# Audio.net
KiCad netlist of a schematic drawn in Altium Designer
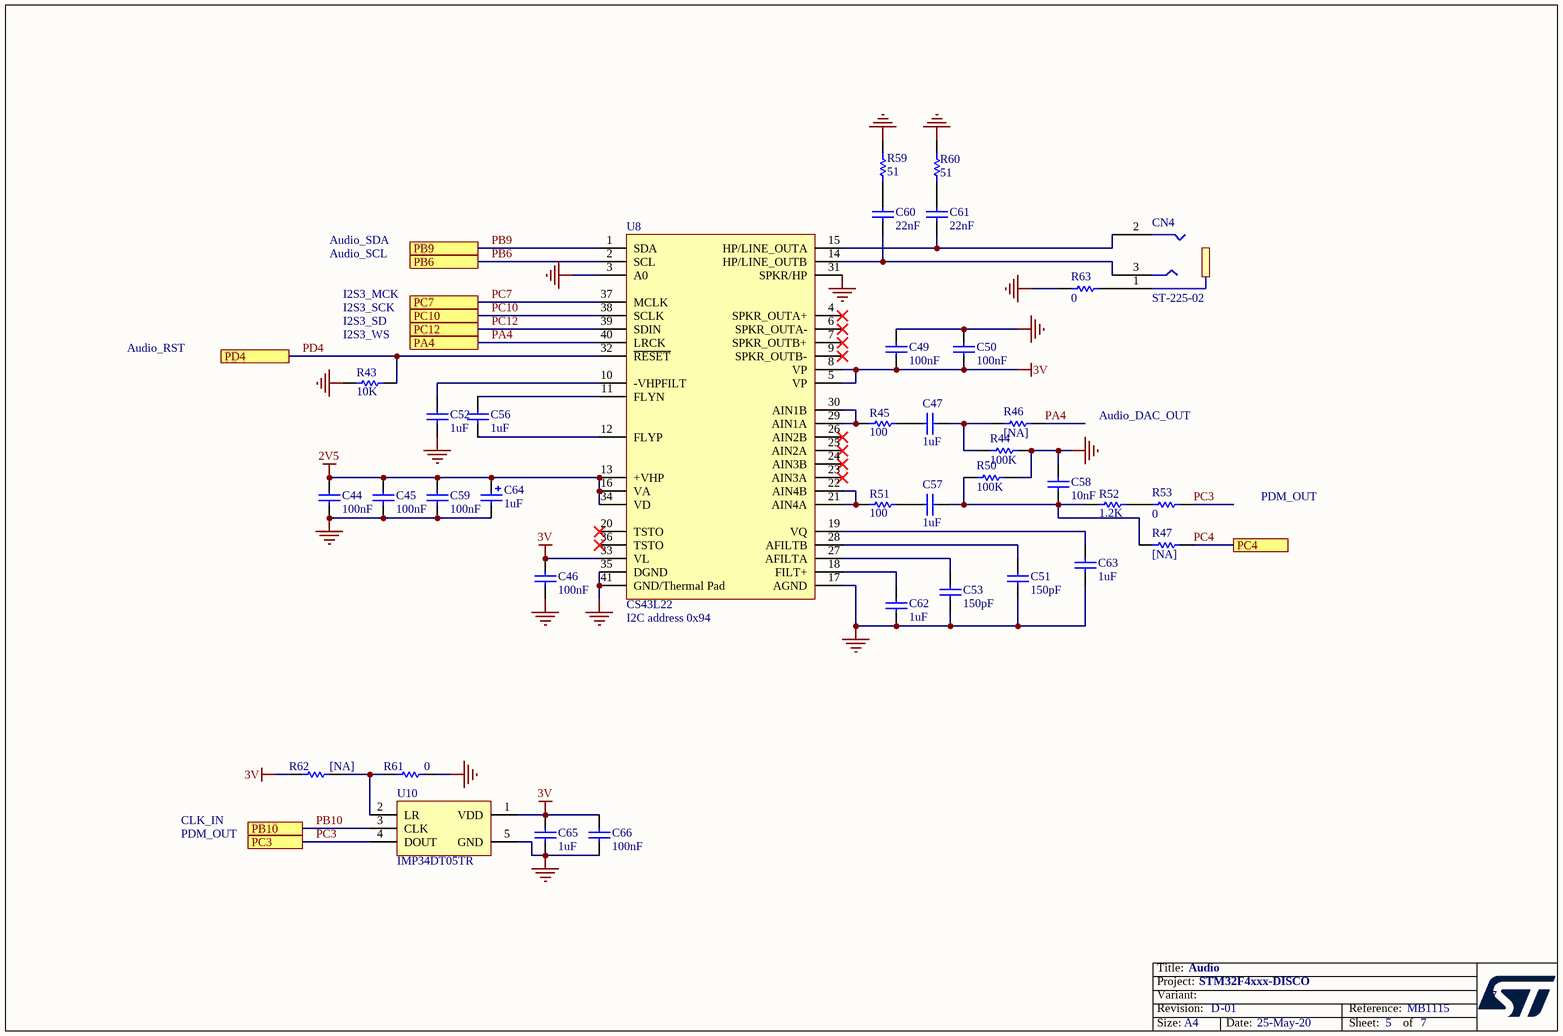
[diagram p0: Audio.SchDoc]

(export (version "E")
  (design (tool "Eeschema 10.0.6"))
  (components
    (comp (ref "C44")
      (value "100nF")
      (footprint "0402C (Primary)")
      (description "Capacitor,100nF,16V,X7R,10%,0402,YAGEO")
      (libsource (lib "MCD_TOOLS") (part "Cap_100nF_X7R_10%_0402"))
    )
    (comp (ref "C45")
      (value "100nF")
      (footprint "0402C (Primary)")
      (description "Capacitor,100nF,16V,X7R,10%,0402,YAGEO")
      (libsource (lib "MCD_TOOLS") (part "Cap_100nF_X7R_10%_0402"))
    )
    (comp (ref "C46")
      (value "100nF")
      (footprint "0402C (Primary)")
      (description "Capacitor,100nF,16V,X7R,10%,0402,YAGEO")
      (libsource (lib "MCD_TOOLS") (part "Cap_100nF_X7R_10%_0402"))
    )
    (comp (ref "C47")
      (value "1uF")
      (footprint "0603C (Primary)")
      (description "Capacitor,1uF,16V,X5R,10%,0603,YAGEO")
      (libsource (lib "MCD_TOOLS") (part "Cap_1uF_X5R_10%_0603"))
    )
    (comp (ref "C49")
      (value "100nF")
      (footprint "0402C (Primary)")
      (description "Capacitor,100nF,16V,X7R,10%,0402,YAGEO")
      (libsource (lib "MCD_TOOLS") (part "Cap_100nF_X7R_10%_0402"))
    )
    (comp (ref "C50")
      (value "100nF")
      (footprint "0402C (Primary)")
      (description "Capacitor,100nF,16V,X7R,10%,0402,YAGEO")
      (libsource (lib "MCD_TOOLS") (part "Cap_100nF_X7R_10%_0402"))
    )
    (comp (ref "C51")
      (value "150pF")
      (footprint "0603C (Primary)")
      (description "Capacitor,150pF,50V,NPO,5%,0603,YAGEO")
      (libsource (lib "MCD_TOOLS") (part "Cap_150pF_NPO_5%_0603"))
    )
    (comp (ref "C52")
      (value "1uF")
      (footprint "0603C (Primary)")
      (description "Capacitor,1uF,16V,X5R,10%,0603,YAGEO")
      (libsource (lib "MCD_TOOLS") (part "Cap_1uF_X5R_10%_0603"))
    )
    (comp (ref "C53")
      (value "150pF")
      (footprint "0603C (Primary)")
      (description "Capacitor,150pF,50V,NPO,5%,0603,YAGEO")
      (libsource (lib "MCD_TOOLS") (part "Cap_150pF_NPO_5%_0603"))
    )
    (comp (ref "C56")
      (value "1uF")
      (footprint "0603C (Primary)")
      (description "Capacitor,1uF,16V,X5R,10%,0603,YAGEO")
      (libsource (lib "MCD_TOOLS") (part "Cap_1uF_X5R_10%_0603"))
    )
    (comp (ref "C57")
      (value "1uF")
      (footprint "0603C (Primary)")
      (description "Capacitor,1uF,16V,X5R,10%,0603,YAGEO")
      (libsource (lib "MCD_TOOLS") (part "Cap_1uF_X5R_10%_0603"))
    )
    (comp (ref "C58")
      (value "10nF")
      (footprint "0603C (Primary)")
      (description "Capacitor,10nF,50V,X7R,10%,0603,YAGEO")
      (libsource (lib "MCD_TOOLS") (part "Cap_10nF_X7R_10%_0603"))
    )
    (comp (ref "C59")
      (value "100nF")
      (footprint "0402C (Primary)")
      (description "Capacitor,100nF,16V,X7R,10%,0402,YAGEO")
      (libsource (lib "MCD_TOOLS") (part "Cap_100nF_X7R_10%_0402"))
    )
    (comp (ref "C60")
      (value "22nF")
      (footprint "0603C (Primary)")
      (description "Capacitor,22nF,50V,X7R,10%,0603,YAGEO")
      (libsource (lib "MCD_TOOLS") (part "Cap_22nF_X7R_10%_0603"))
    )
    (comp (ref "C61")
      (value "22nF")
      (footprint "0603C (Primary)")
      (description "Capacitor,22nF,50V,X7R,10%,0603,YAGEO")
      (libsource (lib "MCD_TOOLS") (part "Cap_22nF_X7R_10%_0603"))
    )
    (comp (ref "C62")
      (value "1uF")
      (footprint "0603C (Primary)")
      (description "Capacitor,1uF,16V,X5R,10%,0603,YAGEO")
      (libsource (lib "MCD_TOOLS") (part "Cap_1uF_X5R_10%_0603"))
    )
    (comp (ref "C63")
      (value "1uF")
      (footprint "0603C (Primary)")
      (description "Capacitor,1uF,16V,X5R,10%,0603,YAGEO")
      (libsource (lib "MCD_TOOLS") (part "Cap_1uF_X5R_10%_0603"))
    )
    (comp (ref "C64")
      (value "1uF")
      (footprint "TAN-A (Primary)")
      (description "Polarized Capacitor,1uF,16V,10%,typeA,AVX")
      (libsource (lib "MCD_TOOLS") (part "Cap_1uF_POL_10%_TANA"))
    )
    (comp (ref "C65")
      (value "1uF")
      (footprint "0603C (Primary)")
      (description "Capacitor,1uF,16V,X5R,10%,0603,YAGEO")
      (libsource (lib "MCD_TOOLS") (part "Cap_1uF_X5R_10%_0603"))
    )
    (comp (ref "C66")
      (value "100nF")
      (footprint "0402C (Primary)")
      (description "Capacitor,100nF,16V,X7R,10%,0402,YAGEO")
      (libsource (lib "MCD_TOOLS") (part "Cap_100nF_X7R_10%_0402"))
    )
    (comp (ref "CN4")
      (value "ST-225-02")
      (footprint "JACK-ST-225 (Primary)")
      (description "Connector Jack 35mm")
      (libsource (lib "MB997") (part "ST-225-02"))
    )
    (comp (ref "R43")
      (value "10K")
      (footprint "0402R (Primary)")
      (description "Resistor")
      (fields (field (name "PUBLISHER") "Altium Limited"))
      (libsource (lib "Miscellaneous Devices") (part "res1"))
    )
    (comp (ref "R44")
      (value "100K")
      (footprint "0402R (Primary)")
      (description "Resistor")
      (fields (field (name "PUBLISHER") "Altium Limited"))
      (libsource (lib "Miscellaneous Devices") (part "res1"))
    )
    (comp (ref "R45")
      (value "100")
      (footprint "0402R (Primary)")
      (description "Resistor")
      (fields (field (name "PUBLISHER") "Altium Limited"))
      (libsource (lib "Miscellaneous Devices") (part "res1"))
    )
    (comp (ref "R46")
      (value "[NA]")
      (footprint "0402R (Primary)")
      (description "Resistor,[NA],0402")
      (libsource (lib "MCD_TOOLS") (part "Res_NA_0402"))
    )
    (comp (ref "R47")
      (value "[NA]")
      (footprint "0402R (Primary)")
      (description "Resistor,[NA],0402")
      (libsource (lib "MCD_TOOLS") (part "Res_NA_0402"))
    )
    (comp (ref "R50")
      (value "100K")
      (footprint "0402R (Primary)")
      (description "Resistor")
      (fields (field (name "PUBLISHER") "Altium Limited"))
      (libsource (lib "Miscellaneous Devices") (part "res1"))
    )
    (comp (ref "R51")
      (value "100")
      (footprint "0402R (Primary)")
      (description "Resistor")
      (fields (field (name "PUBLISHER") "Altium Limited"))
      (libsource (lib "Miscellaneous Devices") (part "res1"))
    )
    (comp (ref "R52")
      (value "1.2K")
      (footprint "0402R (Primary)")
      (description "Resistor")
      (fields (field (name "PUBLISHER") "Altium Limited"))
      (libsource (lib "Miscellaneous Devices") (part "res1"))
    )
    (comp (ref "R53")
      (value "0")
      (footprint "0402R (Primary)")
      (description "Resistor,0,0402")
      (libsource (lib "MCD_TOOLS") (part "Res_0_0402"))
    )
    (comp (ref "R59")
      (value "51")
      (footprint "0402R (Primary)")
      (description "Resistor")
      (fields (field (name "PUBLISHER") "Altium Limited"))
      (libsource (lib "Miscellaneous Devices") (part "res1"))
    )
    (comp (ref "R60")
      (value "51")
      (footprint "0402R (Primary)")
      (description "Resistor")
      (fields (field (name "PUBLISHER") "Altium Limited"))
      (libsource (lib "Miscellaneous Devices") (part "res1"))
    )
    (comp (ref "R61")
      (value "0")
      (footprint "0402R (Primary)")
      (description "Resistor,0,0402")
      (libsource (lib "MCD_TOOLS") (part "Res_0_0402"))
    )
    (comp (ref "R62")
      (value "[NA]")
      (footprint "0402R (Primary)")
      (description "Resistor,[NA],0402")
      (libsource (lib "MCD_TOOLS") (part "Res_NA_0402"))
    )
    (comp (ref "R63")
      (value "0")
      (footprint "0402R (Primary)")
      (description "Resistor,0,0402")
      (libsource (lib "MCD_TOOLS") (part "Res_0_0402"))
    )
    (comp (ref "U8")
      (value "CS43L22")
      (footprint "QFN40_6X6 (Primary)")
      (description "Low Power, Stereo DAC w/Headphone & Speaker Amps")
      (libsource (lib "MCD_TOOLS") (part "CS43L22"))
    )
    (comp (ref "U10")
      (value "IMP34DT05TR")
      (footprint "MIC_HCLGA_3X4X1_4LD")
      (description "MEMS audio sensor omnidirectional digital microphone for industrial applications")
      (fields
        (field (name "INTERNAL_PART_NUMBER") "MCD-01715")
        (field (name "MANUFACTURER") "STMICROELECTRONICS")
        (field (name "PROVIDED_BY") "SUBCO with ST control")
      )
      (libsource (lib "MCD_PARTS_database") (part "IMP34DT05TR"))
    )
  )
  (nets
    (net (code "1") (name "/PA4") (class "Default")
      (node (ref "R46") (pin "2") (pinfunction "2_2") (pintype "passive"))
      (node (ref "U8") (pin "40") (pinfunction "LRCK_40") (pintype "passive"))
    )
    (net (code "2") (name "/PB6") (class "Default")
      (node (ref "U8") (pin "2") (pinfunction "SCL_2") (pintype "passive"))
    )
    (net (code "3") (name "/PB9") (class "Default")
      (node (ref "U8") (pin "1") (pinfunction "SDA_1") (pintype "passive"))
    )
    (net (code "4") (name "/PB10") (class "Default")
      (node (ref "U10") (pin "3") (pinfunction "CLK_3") (pintype "passive"))
    )
    (net (code "5") (name "/PC3") (class "Default")
      (node (ref "R53") (pin "2") (pinfunction "2_2") (pintype "passive"))
      (node (ref "U10") (pin "4") (pinfunction "DOUT_4") (pintype "passive"))
    )
    (net (code "6") (name "/PC4") (class "Default")
      (node (ref "R47") (pin "2") (pinfunction "2_2") (pintype "passive"))
    )
    (net (code "7") (name "/PC7") (class "Default")
      (node (ref "U8") (pin "37") (pinfunction "MCLK_37") (pintype "passive"))
    )
    (net (code "8") (name "/PC10") (class "Default")
      (node (ref "U8") (pin "38") (pinfunction "SCLK_38") (pintype "passive"))
    )
    (net (code "9") (name "/PC12") (class "Default")
      (node (ref "U8") (pin "39") (pinfunction "SDIN_39") (pintype "passive"))
    )
    (net (code "10") (name "/PD4") (class "Default")
      (node (ref "R43") (pin "1") (pinfunction "1_1") (pintype "passive"))
      (node (ref "U8") (pin "32") (pinfunction "~{RESET}_32") (pintype "passive"))
    )
    (net (code "11") (name "2V5") (class "Default")
      (node (ref "C44") (pin "2") (pinfunction "2_2") (pintype "passive"))
      (node (ref "C45") (pin "2") (pinfunction "2_2") (pintype "passive"))
      (node (ref "C59") (pin "2") (pinfunction "2_2") (pintype "passive"))
      (node (ref "C64") (pin "1") (pinfunction "1_1") (pintype "passive"))
      (node (ref "U8") (pin "13") (pinfunction "+VHP_13") (pintype "passive"))
      (node (ref "U8") (pin "16") (pinfunction "VA_16") (pintype "passive"))
      (node (ref "U8") (pin "34") (pinfunction "VD_34") (pintype "passive"))
    )
    (net (code "12") (name "3V") (class "Default")
      (node (ref "C46") (pin "2") (pinfunction "2_2") (pintype "passive"))
      (node (ref "C49") (pin "1") (pinfunction "1_1") (pintype "passive"))
      (node (ref "C50") (pin "2") (pinfunction "2_2") (pintype "passive"))
      (node (ref "C65") (pin "2") (pinfunction "2_2") (pintype "passive"))
      (node (ref "C66") (pin "2") (pinfunction "2_2") (pintype "passive"))
      (node (ref "R62") (pin "2") (pinfunction "2_2") (pintype "passive"))
      (node (ref "U10") (pin "1") (pinfunction "VDD_1") (pintype "passive"))
      (node (ref "U8") (pin "33") (pinfunction "VL_33") (pintype "passive"))
      (node (ref "U8") (pin "5") (pinfunction "VP_5") (pintype "passive"))
      (node (ref "U8") (pin "8") (pinfunction "VP_8") (pintype "passive"))
    )
    (net (code "13") (name "GND") (class "Default")
      (node (ref "C44") (pin "1") (pinfunction "1_1") (pintype "passive"))
      (node (ref "C45") (pin "1") (pinfunction "1_1") (pintype "passive"))
      (node (ref "C46") (pin "1") (pinfunction "1_1") (pintype "passive"))
      (node (ref "C49") (pin "2") (pinfunction "2_2") (pintype "passive"))
      (node (ref "C50") (pin "1") (pinfunction "1_1") (pintype "passive"))
      (node (ref "C51") (pin "1") (pinfunction "1_1") (pintype "passive"))
      (node (ref "C52") (pin "2") (pinfunction "2_2") (pintype "passive"))
      (node (ref "C53") (pin "1") (pinfunction "1_1") (pintype "passive"))
      (node (ref "C58") (pin "2") (pinfunction "2_2") (pintype "passive"))
      (node (ref "C59") (pin "1") (pinfunction "1_1") (pintype "passive"))
      (node (ref "C62") (pin "1") (pinfunction "1_1") (pintype "passive"))
      (node (ref "C63") (pin "1") (pinfunction "1_1") (pintype "passive"))
      (node (ref "C64") (pin "2") (pinfunction "2_2") (pintype "passive"))
      (node (ref "C65") (pin "1") (pinfunction "1_1") (pintype "passive"))
      (node (ref "C66") (pin "1") (pinfunction "1_1") (pintype "passive"))
      (node (ref "R43") (pin "2") (pinfunction "2_2") (pintype "passive"))
      (node (ref "R44") (pin "2") (pinfunction "2_2") (pintype "passive"))
      (node (ref "R50") (pin "2") (pinfunction "2_2") (pintype "passive"))
      (node (ref "R59") (pin "2") (pinfunction "2_2") (pintype "passive"))
      (node (ref "R60") (pin "1") (pinfunction "1_1") (pintype "passive"))
      (node (ref "R61") (pin "1") (pinfunction "1_1") (pintype "passive"))
      (node (ref "R63") (pin "1") (pinfunction "1_1") (pintype "passive"))
      (node (ref "U10") (pin "5") (pinfunction "GND_5") (pintype "passive"))
      (node (ref "U8") (pin "17") (pinfunction "AGND_17") (pintype "passive"))
      (node (ref "U8") (pin "3") (pinfunction "A0_3") (pintype "passive"))
      (node (ref "U8") (pin "31") (pinfunction "SPKR/HP_31") (pintype "passive"))
      (node (ref "U8") (pin "35") (pinfunction "DGND_35") (pintype "passive"))
      (node (ref "U8") (pin "41") (pinfunction "GND/Thermal_Pad_41") (pintype "passive"))
    )
    (net (code "14") (name "Net-(C47-Pad1)") (class "Default")
      (node (ref "C47") (pin "1") (pinfunction "1_1") (pintype "passive"))
      (node (ref "R45") (pin "1") (pinfunction "1_1") (pintype "passive"))
    )
    (net (code "15") (name "Net-(C47-Pad2)") (class "Default")
      (node (ref "C47") (pin "2") (pinfunction "2_2") (pintype "passive"))
      (node (ref "R44") (pin "1") (pinfunction "1_1") (pintype "passive"))
      (node (ref "R46") (pin "1") (pinfunction "1_1") (pintype "passive"))
    )
    (net (code "16") (name "Net-(C57-Pad1)") (class "Default")
      (node (ref "C57") (pin "1") (pinfunction "1_1") (pintype "passive"))
      (node (ref "R51") (pin "1") (pinfunction "1_1") (pintype "passive"))
    )
    (net (code "17") (name "Net-(C57-Pad2)") (class "Default")
      (node (ref "C57") (pin "2") (pinfunction "2_2") (pintype "passive"))
      (node (ref "C58") (pin "1") (pinfunction "1_1") (pintype "passive"))
      (node (ref "R47") (pin "1") (pinfunction "1_1") (pintype "passive"))
      (node (ref "R50") (pin "1") (pinfunction "1_1") (pintype "passive"))
      (node (ref "R52") (pin "1") (pinfunction "1_1") (pintype "passive"))
    )
    (net (code "18") (name "Net-(C60-Pad2)") (class "Default")
      (node (ref "C60") (pin "2") (pinfunction "2_2") (pintype "passive"))
      (node (ref "R59") (pin "1") (pinfunction "1_1") (pintype "passive"))
    )
    (net (code "19") (name "Net-(C61-Pad2)") (class "Default")
      (node (ref "C61") (pin "2") (pinfunction "2_2") (pintype "passive"))
      (node (ref "R60") (pin "2") (pinfunction "2_2") (pintype "passive"))
    )
    (net (code "20") (name "Net-(CN4-Pad1)") (class "Default")
      (node (ref "CN4") (pin "1") (pintype "passive"))
      (node (ref "R63") (pin "2") (pinfunction "2_2") (pintype "passive"))
    )
    (net (code "21") (name "Net-(R52-Pad2)") (class "Default")
      (node (ref "R52") (pin "2") (pinfunction "2_2") (pintype "passive"))
      (node (ref "R53") (pin "1") (pinfunction "1_1") (pintype "passive"))
    )
    (net (code "22") (name "Net-(U8--VHPFILT)") (class "Default")
      (node (ref "C52") (pin "1") (pinfunction "1_1") (pintype "passive"))
      (node (ref "U8") (pin "10") (pinfunction "-VHPFILT_10") (pintype "passive"))
    )
    (net (code "23") (name "Net-(U8-AFILTA)") (class "Default")
      (node (ref "C53") (pin "2") (pinfunction "2_2") (pintype "passive"))
      (node (ref "U8") (pin "27") (pinfunction "AFILTA_27") (pintype "passive"))
    )
    (net (code "24") (name "Net-(U8-AFILTB)") (class "Default")
      (node (ref "C51") (pin "2") (pinfunction "2_2") (pintype "passive"))
      (node (ref "U8") (pin "28") (pinfunction "AFILTB_28") (pintype "passive"))
    )
    (net (code "25") (name "Net-(U8-AIN1A)") (class "Default")
      (node (ref "R45") (pin "2") (pinfunction "2_2") (pintype "passive"))
      (node (ref "U8") (pin "29") (pinfunction "AIN1A_29") (pintype "passive"))
      (node (ref "U8") (pin "30") (pinfunction "AIN1B_30") (pintype "passive"))
    )
    (net (code "26") (name "Net-(U8-AIN4A)") (class "Default")
      (node (ref "R51") (pin "2") (pinfunction "2_2") (pintype "passive"))
      (node (ref "U8") (pin "21") (pinfunction "AIN4A_21") (pintype "passive"))
      (node (ref "U8") (pin "22") (pinfunction "AIN4B_22") (pintype "passive"))
    )
    (net (code "27") (name "Net-(U8-FILT+)") (class "Default")
      (node (ref "C62") (pin "2") (pinfunction "2_2") (pintype "passive"))
      (node (ref "U8") (pin "18") (pinfunction "FILT+_18") (pintype "passive"))
    )
    (net (code "28") (name "Net-(U8-FLYN)") (class "Default")
      (node (ref "C56") (pin "2") (pinfunction "2_2") (pintype "passive"))
      (node (ref "U8") (pin "11") (pinfunction "FLYN_11") (pintype "passive"))
    )
    (net (code "29") (name "Net-(U8-FLYP)") (class "Default")
      (node (ref "C56") (pin "1") (pinfunction "1_1") (pintype "passive"))
      (node (ref "U8") (pin "12") (pinfunction "FLYP_12") (pintype "passive"))
    )
    (net (code "30") (name "Net-(U8-HP{slash}LINE_OUTA)") (class "Default")
      (node (ref "C61") (pin "1") (pinfunction "1_1") (pintype "passive"))
      (node (ref "CN4") (pin "2") (pintype "passive"))
      (node (ref "U8") (pin "15") (pinfunction "HP/LINE_OUTA_15") (pintype "passive"))
    )
    (net (code "31") (name "Net-(U8-HP{slash}LINE_OUTB)") (class "Default")
      (node (ref "C60") (pin "1") (pinfunction "1_1") (pintype "passive"))
      (node (ref "CN4") (pin "3") (pintype "passive"))
      (node (ref "U8") (pin "14") (pinfunction "HP/LINE_OUTB_14") (pintype "passive"))
    )
    (net (code "32") (name "Net-(U8-VQ)") (class "Default")
      (node (ref "C63") (pin "2") (pinfunction "2_2") (pintype "passive"))
      (node (ref "U8") (pin "19") (pinfunction "VQ_19") (pintype "passive"))
    )
    (net (code "33") (name "Net-(U10-LR)") (class "Default")
      (node (ref "R61") (pin "2") (pinfunction "2_2") (pintype "passive"))
      (node (ref "R62") (pin "1") (pinfunction "1_1") (pintype "passive"))
      (node (ref "U10") (pin "2") (pinfunction "LR_2") (pintype "passive"))
    )
    (net (code "34") (name "unconnected-(U8-AIN2A-Pad25)") (class "Default")
      (node (ref "U8") (pin "25") (pinfunction "AIN2A_25") (pintype "passive+no_connect"))
    )
    (net (code "35") (name "unconnected-(U8-AIN2B-Pad26)") (class "Default")
      (node (ref "U8") (pin "26") (pinfunction "AIN2B_26") (pintype "passive+no_connect"))
    )
    (net (code "36") (name "unconnected-(U8-AIN3A-Pad23)") (class "Default")
      (node (ref "U8") (pin "23") (pinfunction "AIN3A_23") (pintype "passive+no_connect"))
    )
    (net (code "37") (name "unconnected-(U8-AIN3B-Pad24)") (class "Default")
      (node (ref "U8") (pin "24") (pinfunction "AIN3B_24") (pintype "passive+no_connect"))
    )
    (net (code "38") (name "unconnected-(U8-SPKR_OUTA+-Pad4)") (class "Default")
      (node (ref "U8") (pin "4") (pinfunction "SPKR_OUTA+_4") (pintype "passive+no_connect"))
    )
    (net (code "39") (name "unconnected-(U8-SPKR_OUTA--Pad6)") (class "Default")
      (node (ref "U8") (pin "6") (pinfunction "SPKR_OUTA-_6") (pintype "passive+no_connect"))
    )
    (net (code "40") (name "unconnected-(U8-SPKR_OUTB+-Pad7)") (class "Default")
      (node (ref "U8") (pin "7") (pinfunction "SPKR_OUTB+_7") (pintype "passive+no_connect"))
    )
    (net (code "41") (name "unconnected-(U8-SPKR_OUTB--Pad9)") (class "Default")
      (node (ref "U8") (pin "9") (pinfunction "SPKR_OUTB-_9") (pintype "passive+no_connect"))
    )
    (net (code "42") (name "unconnected-(U8-TSTO-Pad20)") (class "Default")
      (node (ref "U8") (pin "20") (pinfunction "TSTO_20") (pintype "passive+no_connect"))
    )
    (net (code "43") (name "unconnected-(U8-TSTO-Pad36)") (class "Default")
      (node (ref "U8") (pin "36") (pinfunction "TSTO_36") (pintype "passive+no_connect"))
    )
  )
)
